# 130811_AriloTX_0_0.net
KiCad netlist of a schematic drawn in EAGLE
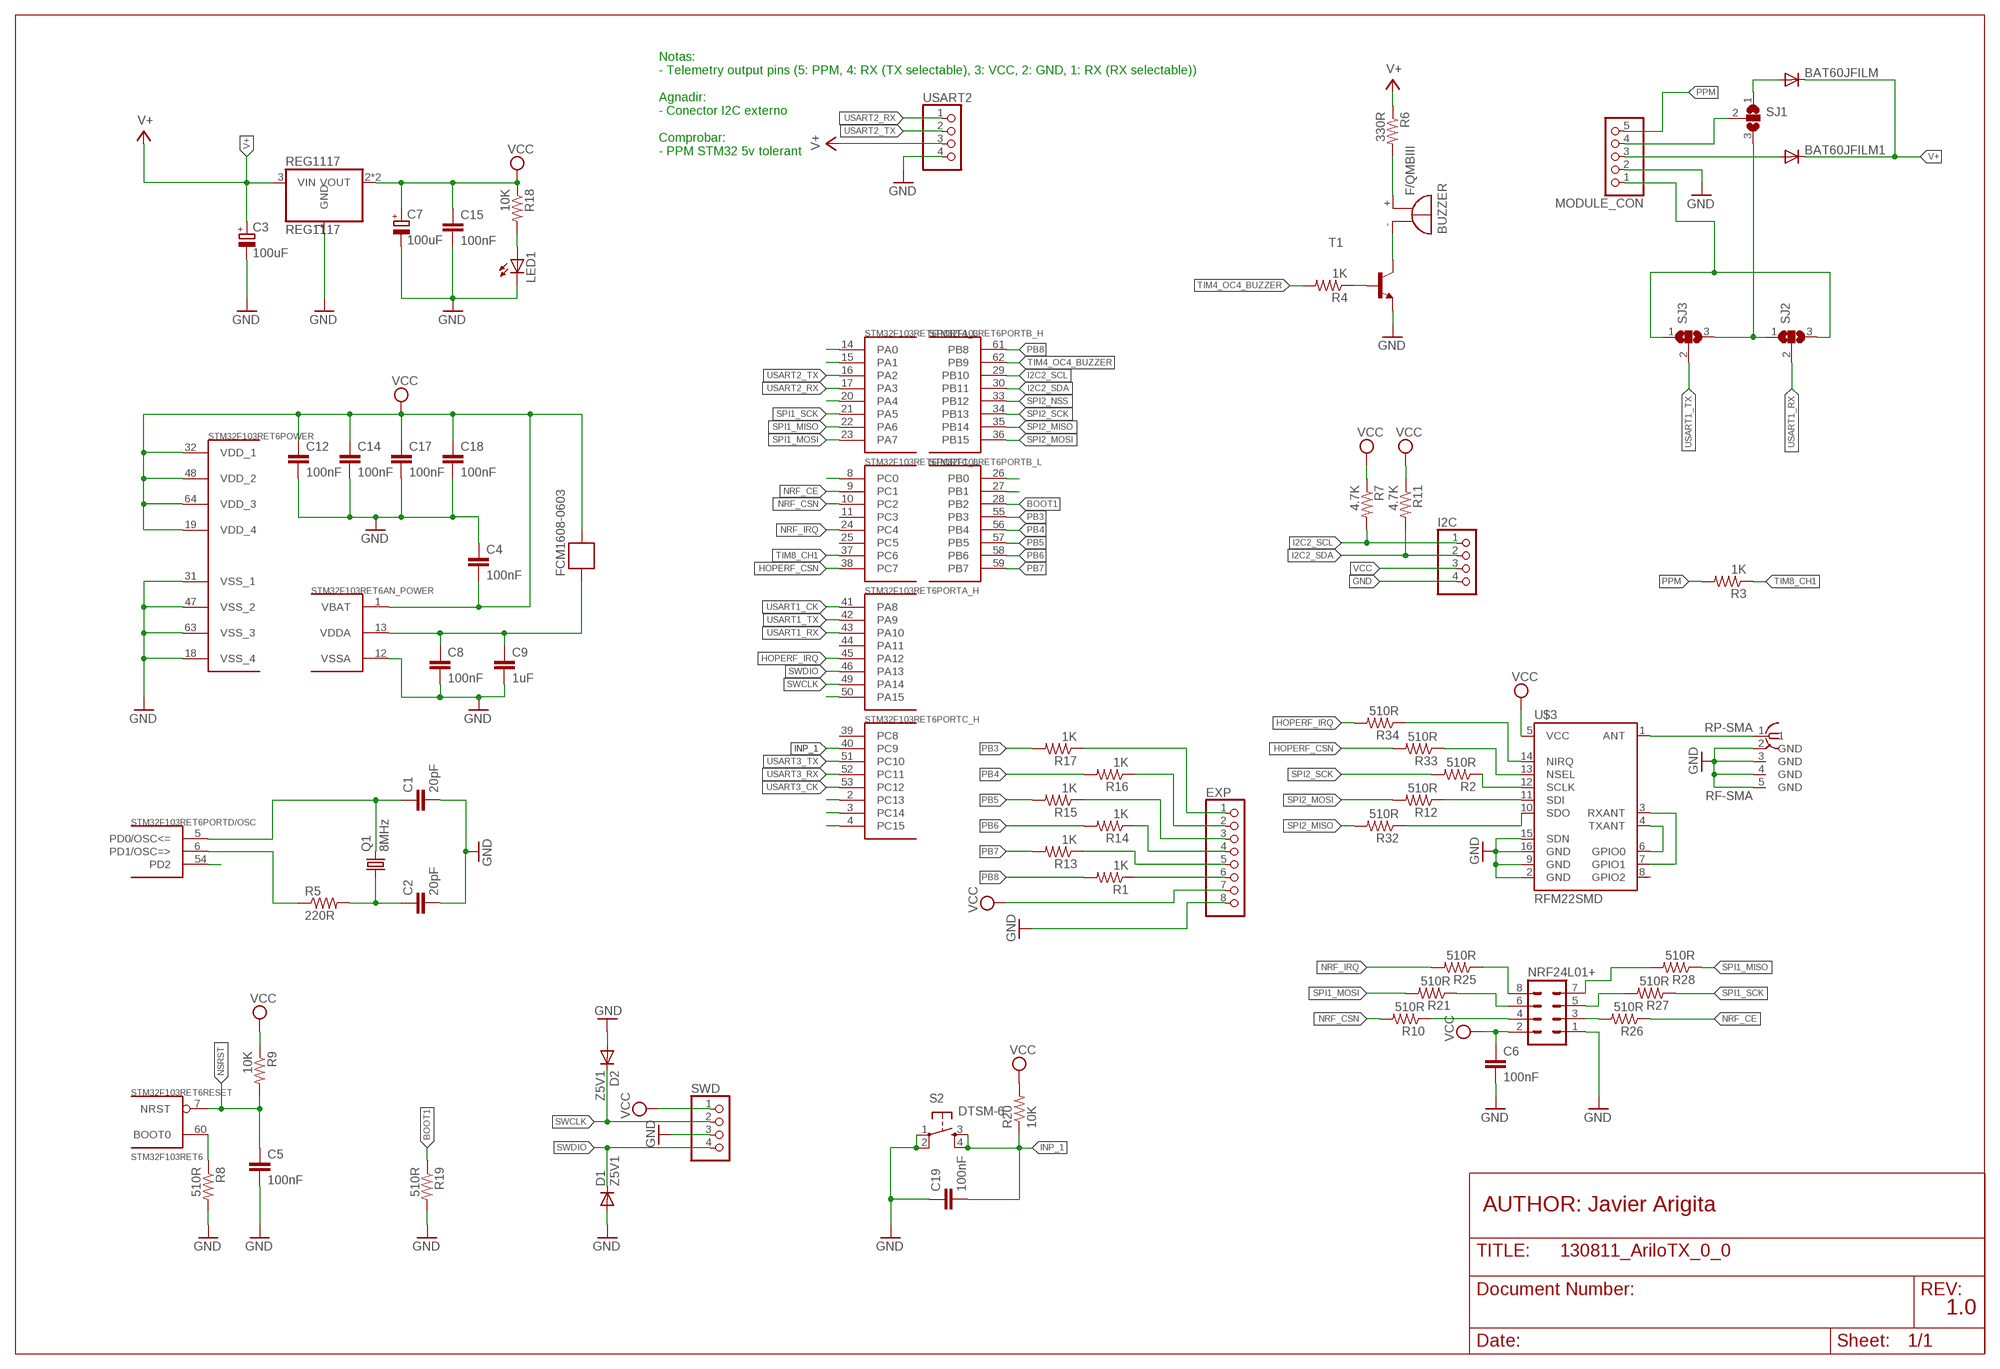
[diagram p0: schematic, sheet 1]

(export (version "E")
  (design (tool "Eeschema 10.0.6"))
  (components
    (comp (ref "BAT60JFILM")
      (value "DIODE-SOD323-R")
      (footprint "eagle-import:SOD323-R")
      (libsource (lib "eagle-import") (part "DIODE-SOD323-R"))
    )
    (comp (ref "BAT60JFILM1")
      (value "DIODE-SOD323-R")
      (footprint "eagle-import:SOD323-R")
      (libsource (lib "eagle-import") (part "DIODE-SOD323-R"))
    )
    (comp (ref "BUZZER")
      (value "F/QMBIII")
      (footprint "eagle-import:F_QMBIII")
      (libsource (lib "eagle-import") (part "F/QMBIII"))
    )
    (comp (ref "C1")
      (value "20pF")
      (footprint "eagle-import:C0805")
      (libsource (lib "eagle-import") (part "C-EUC0805"))
    )
    (comp (ref "C2")
      (value "20pF")
      (footprint "eagle-import:C0805")
      (libsource (lib "eagle-import") (part "C-EUC0805"))
    )
    (comp (ref "C3")
      (value "100uF")
      (footprint "eagle-import:SMC_B")
      (libsource (lib "eagle-import") (part "CPOL-EUSMCB"))
    )
    (comp (ref "C4")
      (value "100nF")
      (footprint "eagle-import:C0805")
      (libsource (lib "eagle-import") (part "C-EUC0805"))
    )
    (comp (ref "C5")
      (value "100nF")
      (footprint "eagle-import:C0805")
      (libsource (lib "eagle-import") (part "C-EUC0805"))
    )
    (comp (ref "C6")
      (value "100nF")
      (footprint "eagle-import:C0805")
      (libsource (lib "eagle-import") (part "C-EUC0805"))
    )
    (comp (ref "C7")
      (value "100uF")
      (footprint "eagle-import:SMC_B")
      (libsource (lib "eagle-import") (part "CPOL-EUSMCB"))
    )
    (comp (ref "C8")
      (value "100nF")
      (footprint "eagle-import:C0805")
      (libsource (lib "eagle-import") (part "C-EUC0805"))
    )
    (comp (ref "C9")
      (value "1uF")
      (footprint "eagle-import:C3216")
      (libsource (lib "eagle-import") (part "resistor_C-EUC3216"))
    )
    (comp (ref "C12")
      (value "100nF")
      (footprint "eagle-import:C0805")
      (libsource (lib "eagle-import") (part "C-EUC0805"))
    )
    (comp (ref "C14")
      (value "100nF")
      (footprint "eagle-import:C0805")
      (libsource (lib "eagle-import") (part "C-EUC0805"))
    )
    (comp (ref "C15")
      (value "100nF")
      (footprint "eagle-import:C0805")
      (libsource (lib "eagle-import") (part "C-EUC0805"))
    )
    (comp (ref "C17")
      (value "100nF")
      (footprint "eagle-import:C0805")
      (libsource (lib "eagle-import") (part "C-EUC0805"))
    )
    (comp (ref "C18")
      (value "100nF")
      (footprint "eagle-import:C0805")
      (libsource (lib "eagle-import") (part "C-EUC0805"))
    )
    (comp (ref "C19")
      (value "100nF")
      (footprint "eagle-import:C0805")
      (libsource (lib "eagle-import") (part "C-EUC0805"))
    )
    (comp (ref "D1")
      (value "Z5V1")
      (footprint "eagle-import:SOD323-R")
      (libsource (lib "eagle-import") (part "DIODE-SOD323-R"))
    )
    (comp (ref "D2")
      (value "Z5V1")
      (footprint "eagle-import:SOD323-R")
      (libsource (lib "eagle-import") (part "DIODE-SOD323-R"))
    )
    (comp (ref "EXP")
      (value "PINHD-1X8")
      (footprint "eagle-import:1X08")
      (libsource (lib "eagle-import") (part "PINHD-1X8"))
    )
    (comp (ref "FCM1608-0603")
      (value "FERRITE-BEAD")
      (footprint "eagle-import:R0603")
      (libsource (lib "eagle-import") (part "FERRITE-BEAD"))
    )
    (comp (ref "I2C")
      (value "PINHD-1X4")
      (footprint "eagle-import:1X04")
      (libsource (lib "eagle-import") (part "PINHD-1X4"))
    )
    (comp (ref "LED1")
      (value "LED0805")
      (footprint "eagle-import:CHIPLED_0805")
      (libsource (lib "eagle-import") (part "LED0805"))
    )
    (comp (ref "MODULE_CON")
      (value "PINHD-1X5")
      (footprint "eagle-import:1X05")
      (libsource (lib "eagle-import") (part "PINHD-1X5"))
    )
    (comp (ref "NRF24L01+")
      (value "MA04-2")
      (footprint "eagle-import:MA04-2")
      (libsource (lib "eagle-import") (part "MA04-2"))
    )
    (comp (ref "Q1")
      (value "8MHz")
      (footprint "eagle-import:SM49")
      (libsource (lib "eagle-import") (part "CRYSTALSM49"))
    )
    (comp (ref "R1")
      (value "1K")
      (footprint "eagle-import:R0805")
      (libsource (lib "eagle-import") (part "RESISTOR0805"))
    )
    (comp (ref "R2")
      (value "510R")
      (footprint "eagle-import:R0805")
      (libsource (lib "eagle-import") (part "RESISTOR0805"))
    )
    (comp (ref "R3")
      (value "1K")
      (footprint "eagle-import:R0805")
      (libsource (lib "eagle-import") (part "RESISTOR0805"))
    )
    (comp (ref "R4")
      (value "1K")
      (footprint "eagle-import:R0805")
      (libsource (lib "eagle-import") (part "RESISTOR0805"))
    )
    (comp (ref "R5")
      (value "220R")
      (footprint "eagle-import:R0805")
      (libsource (lib "eagle-import") (part "RESISTOR0805"))
    )
    (comp (ref "R6")
      (value "330R")
      (footprint "eagle-import:R0805")
      (libsource (lib "eagle-import") (part "RESISTOR0805"))
    )
    (comp (ref "R7")
      (value "4.7K")
      (footprint "eagle-import:R0805")
      (libsource (lib "eagle-import") (part "RESISTOR0805"))
    )
    (comp (ref "R8")
      (value "510R")
      (footprint "eagle-import:R0805")
      (libsource (lib "eagle-import") (part "RESISTOR0805"))
    )
    (comp (ref "R9")
      (value "10K")
      (footprint "eagle-import:R0805")
      (libsource (lib "eagle-import") (part "RESISTOR0805"))
    )
    (comp (ref "R10")
      (value "510R")
      (footprint "eagle-import:R0805")
      (libsource (lib "eagle-import") (part "RESISTOR0805"))
    )
    (comp (ref "R11")
      (value "4.7K")
      (footprint "eagle-import:R0805")
      (libsource (lib "eagle-import") (part "RESISTOR0805"))
    )
    (comp (ref "R12")
      (value "510R")
      (footprint "eagle-import:R0805")
      (libsource (lib "eagle-import") (part "RESISTOR0805"))
    )
    (comp (ref "R13")
      (value "1K")
      (footprint "eagle-import:R0805")
      (libsource (lib "eagle-import") (part "RESISTOR0805"))
    )
    (comp (ref "R14")
      (value "1K")
      (footprint "eagle-import:R0805")
      (libsource (lib "eagle-import") (part "RESISTOR0805"))
    )
    (comp (ref "R15")
      (value "1K")
      (footprint "eagle-import:R0805")
      (libsource (lib "eagle-import") (part "RESISTOR0805"))
    )
    (comp (ref "R16")
      (value "1K")
      (footprint "eagle-import:R0805")
      (libsource (lib "eagle-import") (part "RESISTOR0805"))
    )
    (comp (ref "R17")
      (value "1K")
      (footprint "eagle-import:R0805")
      (libsource (lib "eagle-import") (part "RESISTOR0805"))
    )
    (comp (ref "R18")
      (value "10K")
      (footprint "eagle-import:R0805")
      (libsource (lib "eagle-import") (part "RESISTOR0805"))
    )
    (comp (ref "R19")
      (value "510R")
      (footprint "eagle-import:R0805")
      (libsource (lib "eagle-import") (part "RESISTOR0805"))
    )
    (comp (ref "R20")
      (value "10K")
      (footprint "eagle-import:R0805")
      (libsource (lib "eagle-import") (part "RESISTOR0805"))
    )
    (comp (ref "R21")
      (value "510R")
      (footprint "eagle-import:R0805")
      (libsource (lib "eagle-import") (part "RESISTOR0805"))
    )
    (comp (ref "R25")
      (value "510R")
      (footprint "eagle-import:R0805")
      (libsource (lib "eagle-import") (part "RESISTOR0805"))
    )
    (comp (ref "R26")
      (value "510R")
      (footprint "eagle-import:R0805")
      (libsource (lib "eagle-import") (part "RESISTOR0805"))
    )
    (comp (ref "R27")
      (value "510R")
      (footprint "eagle-import:R0805")
      (libsource (lib "eagle-import") (part "RESISTOR0805"))
    )
    (comp (ref "R28")
      (value "510R")
      (footprint "eagle-import:R0805")
      (libsource (lib "eagle-import") (part "RESISTOR0805"))
    )
    (comp (ref "R32")
      (value "510R")
      (footprint "eagle-import:R0805")
      (libsource (lib "eagle-import") (part "RESISTOR0805"))
    )
    (comp (ref "R33")
      (value "510R")
      (footprint "eagle-import:R0805")
      (libsource (lib "eagle-import") (part "RESISTOR0805"))
    )
    (comp (ref "R34")
      (value "510R")
      (footprint "eagle-import:R0805")
      (libsource (lib "eagle-import") (part "RESISTOR0805"))
    )
    (comp (ref "REG1117")
      (value "REG1117")
      (footprint "eagle-import:SOT223")
      (libsource (lib "eagle-import") (part "REG1117"))
    )
    (comp (ref "RP-SMA")
      (value "RF-SMA")
      (footprint "eagle-import:BU-SMA-H")
      (libsource (lib "eagle-import") (part "RF-SMA"))
    )
    (comp (ref "S2")
      (value "DTSM-6")
      (footprint "eagle-import:DTSM-6")
      (libsource (lib "eagle-import") (part "DTSM-6"))
    )
    (comp (ref "SJ1")
      (value "SJ2W")
      (footprint "eagle-import:SJ_2")
      (libsource (lib "eagle-import") (part "SJ2W"))
    )
    (comp (ref "SJ2")
      (value "SJ2W")
      (footprint "eagle-import:SJ_2")
      (libsource (lib "eagle-import") (part "SJ2W"))
    )
    (comp (ref "SJ3")
      (value "SJ2W")
      (footprint "eagle-import:SJ_2")
      (libsource (lib "eagle-import") (part "SJ2W"))
    )
    (comp (ref "STM32F103RET6")
      (value "STM32F103RET6")
      (footprint "eagle-import:TQFP64")
      (libsource (lib "eagle-import") (part "STM32F10XRXT6"))
    )
    (comp (ref "SWD")
      (value "PINHD-1X4")
      (footprint "eagle-import:1X04")
      (libsource (lib "eagle-import") (part "PINHD-1X4"))
    )
    (comp (ref "T1")
      (value "BC848-NPN-SOT23-BEC")
      (footprint "eagle-import:SOT23-BEC")
      (libsource (lib "eagle-import") (part "-NPN-SOT23-BECBC848"))
    )
    (comp (ref "U$3")
      (value "RFM22SMD")
      (footprint "eagle-import:RFM22-XXX-S2")
      (libsource (lib "eagle-import") (part "RFM22SMD"))
    )
    (comp (ref "USART2")
      (value "PINHD-1X4")
      (footprint "eagle-import:1X04")
      (libsource (lib "eagle-import") (part "PINHD-1X4"))
    )
  )
  (nets
    (net (code "1") (name "BOOT1") (class "Default")
      (node (ref "R19") (pin "1") (pinfunction "1_1") (pintype "passive"))
      (node (ref "STM32F103RET6") (pin "28") (pinfunction "PB2_28") (pintype "bidirectional"))
    )
    (net (code "2") (name "GND") (class "Default")
      (node (ref "C1") (pin "2") (pinfunction "2_2") (pintype "passive"))
      (node (ref "C12") (pin "2") (pinfunction "2_2") (pintype "passive"))
      (node (ref "C14") (pin "2") (pinfunction "2_2") (pintype "passive"))
      (node (ref "C15") (pin "2") (pinfunction "2_2") (pintype "passive"))
      (node (ref "C17") (pin "2") (pinfunction "2_2") (pintype "passive"))
      (node (ref "C18") (pin "2") (pinfunction "2_2") (pintype "passive"))
      (node (ref "C19") (pin "1") (pinfunction "1_1") (pintype "passive"))
      (node (ref "C2") (pin "2") (pinfunction "2_2") (pintype "passive"))
      (node (ref "C3") (pin "-") (pinfunction "-_-") (pintype "passive"))
      (node (ref "C4") (pin "1") (pinfunction "1_1") (pintype "passive"))
      (node (ref "C5") (pin "2") (pinfunction "2_2") (pintype "passive"))
      (node (ref "C6") (pin "2") (pinfunction "2_2") (pintype "passive"))
      (node (ref "C7") (pin "-") (pinfunction "-_-") (pintype "passive"))
      (node (ref "C8") (pin "2") (pinfunction "2_2") (pintype "passive"))
      (node (ref "C9") (pin "2") (pinfunction "2_2") (pintype "passive"))
      (node (ref "D1") (pin "A") (pinfunction "A_A") (pintype "passive"))
      (node (ref "D2") (pin "A") (pinfunction "A_A") (pintype "passive"))
      (node (ref "EXP") (pin "8") (pinfunction "8_8") (pintype "passive"))
      (node (ref "I2C") (pin "4") (pinfunction "4_4") (pintype "passive"))
      (node (ref "LED1") (pin "C") (pinfunction "C_C") (pintype "passive"))
      (node (ref "MODULE_CON") (pin "2") (pinfunction "2_2") (pintype "passive"))
      (node (ref "NRF24L01+") (pin "1") (pinfunction "1_1") (pintype "passive"))
      (node (ref "R19") (pin "2") (pinfunction "2_2") (pintype "passive"))
      (node (ref "R8") (pin "2") (pinfunction "2_2") (pintype "passive"))
      (node (ref "REG1117") (pin "1") (pinfunction "GND_1") (pintype "power_in"))
      (node (ref "RP-SMA") (pin "2") (pinfunction "GND_2") (pintype "power_in"))
      (node (ref "RP-SMA") (pin "3") (pinfunction "GND_3") (pintype "bidirectional"))
      (node (ref "RP-SMA") (pin "4") (pinfunction "GND_4") (pintype "bidirectional"))
      (node (ref "RP-SMA") (pin "5") (pinfunction "GND_5") (pintype "bidirectional"))
      (node (ref "S2") (pin "1") (pinfunction "1_1") (pintype "passive"))
      (node (ref "S2") (pin "2") (pinfunction "2_2") (pintype "passive"))
      (node (ref "STM32F103RET6") (pin "12") (pinfunction "VSSA_12") (pintype "power_in"))
      (node (ref "STM32F103RET6") (pin "18") (pinfunction "VSS_4_18") (pintype "power_in"))
      (node (ref "STM32F103RET6") (pin "31") (pinfunction "VSS_1_31") (pintype "power_in"))
      (node (ref "STM32F103RET6") (pin "47") (pinfunction "VSS_2_47") (pintype "power_in"))
      (node (ref "STM32F103RET6") (pin "63") (pinfunction "VSS_3_63") (pintype "power_in"))
      (node (ref "SWD") (pin "3") (pinfunction "3_3") (pintype "passive"))
      (node (ref "T1") (pin "E") (pinfunction "E_E") (pintype "passive"))
      (node (ref "U$3") (pin "15") (pinfunction "SDN_15") (pintype "input"))
      (node (ref "U$3") (pin "16") (pinfunction "GND_16") (pintype "power_in"))
      (node (ref "U$3") (pin "2") (pinfunction "GND_2") (pintype "power_in"))
      (node (ref "U$3") (pin "9") (pinfunction "GND_9") (pintype "power_in"))
      (node (ref "USART2") (pin "4") (pinfunction "4_4") (pintype "passive"))
    )
    (net (code "3") (name "HOPERF_CSN") (class "Default")
      (node (ref "R33") (pin "2") (pinfunction "2_2") (pintype "passive"))
      (node (ref "STM32F103RET6") (pin "38") (pinfunction "PC7_38") (pintype "bidirectional"))
    )
    (net (code "4") (name "HOPERF_IRQ") (class "Default")
      (node (ref "R34") (pin "2") (pinfunction "2_2") (pintype "passive"))
      (node (ref "STM32F103RET6") (pin "45") (pinfunction "PA12_45") (pintype "bidirectional"))
    )
    (net (code "5") (name "I2C2_SCL") (class "Default")
      (node (ref "I2C") (pin "1") (pinfunction "1_1") (pintype "passive"))
      (node (ref "R7") (pin "2") (pinfunction "2_2") (pintype "passive"))
      (node (ref "STM32F103RET6") (pin "29") (pinfunction "PB10_29") (pintype "bidirectional"))
    )
    (net (code "6") (name "I2C2_SDA") (class "Default")
      (node (ref "I2C") (pin "2") (pinfunction "2_2") (pintype "passive"))
      (node (ref "R11") (pin "2") (pinfunction "2_2") (pintype "passive"))
      (node (ref "STM32F103RET6") (pin "30") (pinfunction "PB11_30") (pintype "bidirectional"))
    )
    (net (code "7") (name "INP_1") (class "Default")
      (node (ref "C19") (pin "2") (pinfunction "2_2") (pintype "passive"))
      (node (ref "R20") (pin "1") (pinfunction "1_1") (pintype "passive"))
      (node (ref "S2") (pin "3") (pinfunction "3_3") (pintype "passive"))
      (node (ref "S2") (pin "4") (pinfunction "4_4") (pintype "passive"))
      (node (ref "STM32F103RET6") (pin "40") (pinfunction "PC9_40") (pintype "bidirectional"))
    )
    (net (code "8") (name "NRF_CE") (class "Default")
      (node (ref "R26") (pin "1") (pinfunction "1_1") (pintype "passive"))
      (node (ref "STM32F103RET6") (pin "9") (pinfunction "PC1_9") (pintype "bidirectional"))
    )
    (net (code "9") (name "NRF_CSN") (class "Default")
      (node (ref "R10") (pin "2") (pinfunction "2_2") (pintype "passive"))
      (node (ref "STM32F103RET6") (pin "10") (pinfunction "PC2_10") (pintype "bidirectional"))
    )
    (net (code "10") (name "NRF_IRQ") (class "Default")
      (node (ref "R25") (pin "2") (pinfunction "2_2") (pintype "passive"))
      (node (ref "STM32F103RET6") (pin "24") (pinfunction "PC4_24") (pintype "bidirectional"))
    )
    (net (code "11") (name "NSRST") (class "Default")
      (node (ref "C5") (pin "1") (pinfunction "1_1") (pintype "passive"))
      (node (ref "R9") (pin "2") (pinfunction "2_2") (pintype "passive"))
      (node (ref "STM32F103RET6") (pin "7") (pinfunction "NRST_7") (pintype "input"))
    )
    (net (code "12") (name "Net-(BAT60JFILM-PadA)") (class "Default")
      (node (ref "BAT60JFILM") (pin "A") (pinfunction "A_A") (pintype "passive"))
      (node (ref "SJ1") (pin "1") (pinfunction "1_1") (pintype "passive"))
    )
    (net (code "13") (name "Net-(BAT60JFILM1-PadA)") (class "Default")
      (node (ref "BAT60JFILM1") (pin "A") (pinfunction "A_A") (pintype "passive"))
      (node (ref "MODULE_CON") (pin "3") (pinfunction "3_3") (pintype "passive"))
    )
    (net (code "14") (name "Net-(BUZZER-+)") (class "Default")
      (node (ref "BUZZER") (pin "-") (pinfunction "+_-") (pintype "passive"))
      (node (ref "T1") (pin "C") (pinfunction "C_C") (pintype "passive"))
    )
    (net (code "15") (name "Net-(BUZZER--)") (class "Default")
      (node (ref "BUZZER") (pin "+") (pinfunction "-_+") (pintype "passive"))
      (node (ref "R6") (pin "2") (pinfunction "2_2") (pintype "passive"))
    )
    (net (code "16") (name "Net-(C2-Pad1)") (class "Default")
      (node (ref "C2") (pin "1") (pinfunction "1_1") (pintype "passive"))
      (node (ref "Q1") (pin "1") (pinfunction "1_1") (pintype "passive"))
      (node (ref "R5") (pin "2") (pinfunction "2_2") (pintype "passive"))
    )
    (net (code "17") (name "Net-(EXP-Pad1)") (class "Default")
      (node (ref "EXP") (pin "1") (pinfunction "1_1") (pintype "passive"))
      (node (ref "R17") (pin "1") (pinfunction "1_1") (pintype "passive"))
    )
    (net (code "18") (name "Net-(EXP-Pad2)") (class "Default")
      (node (ref "EXP") (pin "2") (pinfunction "2_2") (pintype "passive"))
      (node (ref "R16") (pin "1") (pinfunction "1_1") (pintype "passive"))
    )
    (net (code "19") (name "Net-(EXP-Pad3)") (class "Default")
      (node (ref "EXP") (pin "3") (pinfunction "3_3") (pintype "passive"))
      (node (ref "R15") (pin "1") (pinfunction "1_1") (pintype "passive"))
    )
    (net (code "20") (name "Net-(EXP-Pad4)") (class "Default")
      (node (ref "EXP") (pin "4") (pinfunction "4_4") (pintype "passive"))
      (node (ref "R14") (pin "1") (pinfunction "1_1") (pintype "passive"))
    )
    (net (code "21") (name "Net-(EXP-Pad5)") (class "Default")
      (node (ref "EXP") (pin "5") (pinfunction "5_5") (pintype "passive"))
      (node (ref "R13") (pin "1") (pinfunction "1_1") (pintype "passive"))
    )
    (net (code "22") (name "Net-(EXP-Pad6)") (class "Default")
      (node (ref "EXP") (pin "6") (pinfunction "6_6") (pintype "passive"))
      (node (ref "R1") (pin "1") (pinfunction "1_1") (pintype "passive"))
    )
    (net (code "23") (name "Net-(FCM1608-0603-P$2)") (class "Default")
      (node (ref "C8") (pin "1") (pinfunction "1_1") (pintype "passive"))
      (node (ref "C9") (pin "1") (pinfunction "1_1") (pintype "passive"))
      (node (ref "FCM1608-0603") (pin "2") (pinfunction "P$2_2") (pintype "bidirectional"))
      (node (ref "STM32F103RET6") (pin "13") (pinfunction "VDDA_13") (pintype "power_in"))
    )
    (net (code "24") (name "Net-(LED1-PadA)") (class "Default")
      (node (ref "LED1") (pin "A") (pinfunction "A_A") (pintype "passive"))
      (node (ref "R18") (pin "2") (pinfunction "2_2") (pintype "passive"))
    )
    (net (code "25") (name "Net-(MODULE_CON-Pad1)") (class "Default")
      (node (ref "MODULE_CON") (pin "1") (pinfunction "1_1") (pintype "passive"))
      (node (ref "SJ2") (pin "3") (pinfunction "3_3") (pintype "passive"))
      (node (ref "SJ3") (pin "1") (pinfunction "1_1") (pintype "passive"))
    )
    (net (code "26") (name "Net-(MODULE_CON-Pad4)") (class "Default")
      (node (ref "MODULE_CON") (pin "4") (pinfunction "4_4") (pintype "passive"))
      (node (ref "SJ1") (pin "2") (pinfunction "2_2") (pintype "passive"))
    )
    (net (code "27") (name "Net-(NRF24L01+-Pad3)") (class "Default")
      (node (ref "NRF24L01+") (pin "3") (pinfunction "3_3") (pintype "passive"))
      (node (ref "R26") (pin "2") (pinfunction "2_2") (pintype "passive"))
    )
    (net (code "28") (name "Net-(NRF24L01+-Pad4)") (class "Default")
      (node (ref "NRF24L01+") (pin "4") (pinfunction "4_4") (pintype "passive"))
      (node (ref "R10") (pin "1") (pinfunction "1_1") (pintype "passive"))
    )
    (net (code "29") (name "Net-(NRF24L01+-Pad5)") (class "Default")
      (node (ref "NRF24L01+") (pin "5") (pinfunction "5_5") (pintype "passive"))
      (node (ref "R27") (pin "2") (pinfunction "2_2") (pintype "passive"))
    )
    (net (code "30") (name "Net-(NRF24L01+-Pad6)") (class "Default")
      (node (ref "NRF24L01+") (pin "6") (pinfunction "6_6") (pintype "passive"))
      (node (ref "R21") (pin "1") (pinfunction "1_1") (pintype "passive"))
    )
    (net (code "31") (name "Net-(NRF24L01+-Pad7)") (class "Default")
      (node (ref "NRF24L01+") (pin "7") (pinfunction "7_7") (pintype "passive"))
      (node (ref "R28") (pin "2") (pinfunction "2_2") (pintype "passive"))
    )
    (net (code "32") (name "Net-(NRF24L01+-Pad8)") (class "Default")
      (node (ref "NRF24L01+") (pin "8") (pinfunction "8_8") (pintype "passive"))
      (node (ref "R25") (pin "1") (pinfunction "1_1") (pintype "passive"))
    )
    (net (code "33") (name "Net-(R4-Pad1)") (class "Default")
      (node (ref "R4") (pin "1") (pinfunction "1_1") (pintype "passive"))
      (node (ref "T1") (pin "B") (pinfunction "B_B") (pintype "passive"))
    )
    (net (code "34") (name "Net-(SJ1-Pad3)") (class "Default")
      (node (ref "SJ1") (pin "3") (pinfunction "3_3") (pintype "passive"))
      (node (ref "SJ2") (pin "1") (pinfunction "1_1") (pintype "passive"))
      (node (ref "SJ3") (pin "3") (pinfunction "3_3") (pintype "passive"))
    )
    (net (code "35") (name "Net-(STM32F103RET6H-PD0{slash}OSC<=)") (class "Default")
      (node (ref "C1") (pin "1") (pinfunction "1_1") (pintype "passive"))
      (node (ref "Q1") (pin "2") (pinfunction "2_2") (pintype "passive"))
      (node (ref "STM32F103RET6") (pin "5") (pinfunction "PD0/OSC<=_5") (pintype "bidirectional"))
    )
    (net (code "36") (name "Net-(STM32F103RET6H-PD1{slash}OSC=>)") (class "Default")
      (node (ref "R5") (pin "1") (pinfunction "1_1") (pintype "passive"))
      (node (ref "STM32F103RET6") (pin "6") (pinfunction "PD1/OSC=>_6") (pintype "bidirectional"))
    )
    (net (code "37") (name "Net-(STM32F103RET6J-BOOT0)") (class "Default")
      (node (ref "R8") (pin "1") (pinfunction "1_1") (pintype "passive"))
      (node (ref "STM32F103RET6") (pin "60") (pinfunction "BOOT0_60") (pintype "input"))
    )
    (net (code "38") (name "Net-(U$3-ANT)") (class "Default")
      (node (ref "RP-SMA") (pin "1") (pinfunction "1_1") (pintype "passive"))
      (node (ref "U$3") (pin "1") (pinfunction "ANT_1") (pintype "bidirectional"))
    )
    (net (code "39") (name "Net-(U$3-GPIO0)") (class "Default")
      (node (ref "U$3") (pin "4") (pinfunction "TXANT_4") (pintype "input"))
      (node (ref "U$3") (pin "6") (pinfunction "GPIO0_6") (pintype "bidirectional"))
    )
    (net (code "40") (name "Net-(U$3-GPIO1)") (class "Default")
      (node (ref "U$3") (pin "3") (pinfunction "RXANT_3") (pintype "input"))
      (node (ref "U$3") (pin "7") (pinfunction "GPIO1_7") (pintype "bidirectional"))
    )
    (net (code "41") (name "Net-(U$3-NIRQ)") (class "Default")
      (node (ref "R34") (pin "1") (pinfunction "1_1") (pintype "passive"))
      (node (ref "U$3") (pin "14") (pinfunction "NIRQ_14") (pintype "output"))
    )
    (net (code "42") (name "Net-(U$3-NSEL)") (class "Default")
      (node (ref "R33") (pin "1") (pinfunction "1_1") (pintype "passive"))
      (node (ref "U$3") (pin "13") (pinfunction "NSEL_13") (pintype "input"))
    )
    (net (code "43") (name "Net-(U$3-SCLK)") (class "Default")
      (node (ref "R2") (pin "1") (pinfunction "1_1") (pintype "passive"))
      (node (ref "U$3") (pin "12") (pinfunction "SCLK_12") (pintype "input"))
    )
    (net (code "44") (name "Net-(U$3-SDI)") (class "Default")
      (node (ref "R12") (pin "1") (pinfunction "1_1") (pintype "passive"))
      (node (ref "U$3") (pin "11") (pinfunction "SDI_11") (pintype "input"))
    )
    (net (code "45") (name "Net-(U$3-SDO)") (class "Default")
      (node (ref "R32") (pin "1") (pinfunction "1_1") (pintype "passive"))
      (node (ref "U$3") (pin "10") (pinfunction "SDO_10") (pintype "output"))
    )
    (net (code "46") (name "PB3") (class "Default")
      (node (ref "R17") (pin "2") (pinfunction "2_2") (pintype "passive"))
      (node (ref "STM32F103RET6") (pin "55") (pinfunction "PB3_55") (pintype "bidirectional"))
    )
    (net (code "47") (name "PB4") (class "Default")
      (node (ref "R16") (pin "2") (pinfunction "2_2") (pintype "passive"))
      (node (ref "STM32F103RET6") (pin "56") (pinfunction "PB4_56") (pintype "bidirectional"))
    )
    (net (code "48") (name "PB5") (class "Default")
      (node (ref "R15") (pin "2") (pinfunction "2_2") (pintype "passive"))
      (node (ref "STM32F103RET6") (pin "57") (pinfunction "PB5_57") (pintype "bidirectional"))
    )
    (net (code "49") (name "PB6") (class "Default")
      (node (ref "R14") (pin "2") (pinfunction "2_2") (pintype "passive"))
      (node (ref "STM32F103RET6") (pin "58") (pinfunction "PB6_58") (pintype "bidirectional"))
    )
    (net (code "50") (name "PB7") (class "Default")
      (node (ref "R13") (pin "2") (pinfunction "2_2") (pintype "passive"))
      (node (ref "STM32F103RET6") (pin "59") (pinfunction "PB7_59") (pintype "bidirectional"))
    )
    (net (code "51") (name "PB8") (class "Default")
      (node (ref "R1") (pin "2") (pinfunction "2_2") (pintype "passive"))
      (node (ref "STM32F103RET6") (pin "61") (pinfunction "PB8_61") (pintype "bidirectional"))
    )
    (net (code "52") (name "PPM") (class "Default")
      (node (ref "MODULE_CON") (pin "5") (pinfunction "5_5") (pintype "passive"))
      (node (ref "R3") (pin "2") (pinfunction "2_2") (pintype "passive"))
    )
    (net (code "53") (name "SPI1_MISO") (class "Default")
      (node (ref "R28") (pin "1") (pinfunction "1_1") (pintype "passive"))
      (node (ref "STM32F103RET6") (pin "22") (pinfunction "PA6_22") (pintype "bidirectional"))
    )
    (net (code "54") (name "SPI1_MOSI") (class "Default")
      (node (ref "R21") (pin "2") (pinfunction "2_2") (pintype "passive"))
      (node (ref "STM32F103RET6") (pin "23") (pinfunction "PA7_23") (pintype "bidirectional"))
    )
    (net (code "55") (name "SPI1_SCK") (class "Default")
      (node (ref "R27") (pin "1") (pinfunction "1_1") (pintype "passive"))
      (node (ref "STM32F103RET6") (pin "21") (pinfunction "PA5_21") (pintype "bidirectional"))
    )
    (net (code "56") (name "SPI2_MISO") (class "Default")
      (node (ref "R32") (pin "2") (pinfunction "2_2") (pintype "passive"))
      (node (ref "STM32F103RET6") (pin "35") (pinfunction "PB14_35") (pintype "bidirectional"))
    )
    (net (code "57") (name "SPI2_MOSI") (class "Default")
      (node (ref "R12") (pin "2") (pinfunction "2_2") (pintype "passive"))
      (node (ref "STM32F103RET6") (pin "36") (pinfunction "PB15_36") (pintype "bidirectional"))
    )
    (net (code "58") (name "SPI2_NSS") (class "Default")
      (node (ref "STM32F103RET6") (pin "33") (pinfunction "PB12_33") (pintype "bidirectional"))
    )
    (net (code "59") (name "SPI2_SCK") (class "Default")
      (node (ref "R2") (pin "2") (pinfunction "2_2") (pintype "passive"))
      (node (ref "STM32F103RET6") (pin "34") (pinfunction "PB13_34") (pintype "bidirectional"))
    )
    (net (code "60") (name "SWCLK") (class "Default")
      (node (ref "D2") (pin "C") (pinfunction "C_C") (pintype "passive"))
      (node (ref "STM32F103RET6") (pin "49") (pinfunction "PA14_49") (pintype "bidirectional"))
      (node (ref "SWD") (pin "2") (pinfunction "2_2") (pintype "passive"))
    )
    (net (code "61") (name "SWDIO") (class "Default")
      (node (ref "D1") (pin "C") (pinfunction "C_C") (pintype "passive"))
      (node (ref "STM32F103RET6") (pin "46") (pinfunction "PA13_46") (pintype "bidirectional"))
      (node (ref "SWD") (pin "4") (pinfunction "4_4") (pintype "passive"))
    )
    (net (code "62") (name "TIM4_OC4_BUZZER") (class "Default")
      (node (ref "R4") (pin "2") (pinfunction "2_2") (pintype "passive"))
      (node (ref "STM32F103RET6") (pin "62") (pinfunction "PB9_62") (pintype "bidirectional"))
    )
    (net (code "63") (name "TIM8_CH1") (class "Default")
      (node (ref "R3") (pin "1") (pinfunction "1_1") (pintype "passive"))
      (node (ref "STM32F103RET6") (pin "37") (pinfunction "PC6_37") (pintype "bidirectional"))
    )
    (net (code "64") (name "USART1_CK") (class "Default")
      (node (ref "STM32F103RET6") (pin "41") (pinfunction "PA8_41") (pintype "bidirectional"))
    )
    (net (code "65") (name "USART1_RX") (class "Default")
      (node (ref "SJ2") (pin "2") (pinfunction "2_2") (pintype "passive"))
      (node (ref "STM32F103RET6") (pin "43") (pinfunction "PA10_43") (pintype "bidirectional"))
    )
    (net (code "66") (name "USART1_TX") (class "Default")
      (node (ref "SJ3") (pin "2") (pinfunction "2_2") (pintype "passive"))
      (node (ref "STM32F103RET6") (pin "42") (pinfunction "PA9_42") (pintype "bidirectional"))
    )
    (net (code "67") (name "USART2_RX") (class "Default")
      (node (ref "STM32F103RET6") (pin "17") (pinfunction "PA3_17") (pintype "bidirectional"))
      (node (ref "USART2") (pin "1") (pinfunction "1_1") (pintype "passive"))
    )
    (net (code "68") (name "USART2_TX") (class "Default")
      (node (ref "STM32F103RET6") (pin "16") (pinfunction "PA2_16") (pintype "bidirectional"))
      (node (ref "USART2") (pin "2") (pinfunction "2_2") (pintype "passive"))
    )
    (net (code "69") (name "USART3_CK") (class "Default")
      (node (ref "STM32F103RET6") (pin "53") (pinfunction "PC12_53") (pintype "bidirectional"))
    )
    (net (code "70") (name "USART3_RX") (class "Default")
      (node (ref "STM32F103RET6") (pin "52") (pinfunction "PC11_52") (pintype "bidirectional"))
    )
    (net (code "71") (name "USART3_TX") (class "Default")
      (node (ref "STM32F103RET6") (pin "51") (pinfunction "PC10_51") (pintype "bidirectional"))
    )
    (net (code "72") (name "V+") (class "Default")
      (node (ref "BAT60JFILM") (pin "C") (pinfunction "C_C") (pintype "passive"))
      (node (ref "BAT60JFILM1") (pin "C") (pinfunction "C_C") (pintype "passive"))
      (node (ref "C3") (pin "+") (pinfunction "+_+") (pintype "passive"))
      (node (ref "R6") (pin "1") (pinfunction "1_1") (pintype "passive"))
      (node (ref "REG1117") (pin "3") (pinfunction "VIN_3") (pintype "input"))
      (node (ref "USART2") (pin "3") (pinfunction "3_3") (pintype "passive"))
    )
    (net (code "73") (name "VCC") (class "Default")
      (node (ref "C12") (pin "1") (pinfunction "1_1") (pintype "passive"))
      (node (ref "C14") (pin "1") (pinfunction "1_1") (pintype "passive"))
      (node (ref "C15") (pin "1") (pinfunction "1_1") (pintype "passive"))
      (node (ref "C17") (pin "1") (pinfunction "1_1") (pintype "passive"))
      (node (ref "C18") (pin "1") (pinfunction "1_1") (pintype "passive"))
      (node (ref "C4") (pin "2") (pinfunction "2_2") (pintype "passive"))
      (node (ref "C6") (pin "1") (pinfunction "1_1") (pintype "passive"))
      (node (ref "C7") (pin "+") (pinfunction "+_+") (pintype "passive"))
      (node (ref "EXP") (pin "7") (pinfunction "7_7") (pintype "passive"))
      (node (ref "FCM1608-0603") (pin "1") (pinfunction "P$1_1") (pintype "bidirectional"))
      (node (ref "I2C") (pin "3") (pinfunction "3_3") (pintype "passive"))
      (node (ref "NRF24L01+") (pin "2") (pinfunction "2_2") (pintype "passive"))
      (node (ref "R11") (pin "1") (pinfunction "1_1") (pintype "passive"))
      (node (ref "R18") (pin "1") (pinfunction "1_1") (pintype "passive"))
      (node (ref "R20") (pin "2") (pinfunction "2_2") (pintype "passive"))
      (node (ref "R7") (pin "1") (pinfunction "1_1") (pintype "passive"))
      (node (ref "R9") (pin "1") (pinfunction "1_1") (pintype "passive"))
      (node (ref "REG1117") (pin "2") (pinfunction "VOUT_2") (pintype "power_in"))
      (node (ref "REG1117") (pin "4") (pinfunction "VOUT_4") (pintype "power_in"))
      (node (ref "STM32F103RET6") (pin "1") (pinfunction "VBAT_1") (pintype "power_in"))
      (node (ref "STM32F103RET6") (pin "19") (pinfunction "VDD_4_19") (pintype "power_in"))
      (node (ref "STM32F103RET6") (pin "32") (pinfunction "VDD_1_32") (pintype "power_in"))
      (node (ref "STM32F103RET6") (pin "48") (pinfunction "VDD_2_48") (pintype "power_in"))
      (node (ref "STM32F103RET6") (pin "64") (pinfunction "VDD_3_64") (pintype "power_in"))
      (node (ref "SWD") (pin "1") (pinfunction "1_1") (pintype "passive"))
      (node (ref "U$3") (pin "5") (pinfunction "VCC_5") (pintype "bidirectional"))
    )
    (net (code "74") (name "unconnected-(STM32F103RET6B-PA11-Pad44)") (class "Default")
      (node (ref "STM32F103RET6") (pin "44") (pinfunction "PA11_44") (pintype "bidirectional"))
    )
    (net (code "75") (name "unconnected-(STM32F103RET6B-PA15-Pad50)") (class "Default")
      (node (ref "STM32F103RET6") (pin "50") (pinfunction "PA15_50") (pintype "bidirectional"))
    )
    (net (code "76") (name "unconnected-(STM32F103RET6C-PA0-Pad14)") (class "Default")
      (node (ref "STM32F103RET6") (pin "14") (pinfunction "PA0_14") (pintype "bidirectional"))
    )
    (net (code "77") (name "unconnected-(STM32F103RET6C-PA1-Pad15)") (class "Default")
      (node (ref "STM32F103RET6") (pin "15") (pinfunction "PA1_15") (pintype "bidirectional"))
    )
    (net (code "78") (name "unconnected-(STM32F103RET6C-PA4-Pad20)") (class "Default")
      (node (ref "STM32F103RET6") (pin "20") (pinfunction "PA4_20") (pintype "bidirectional"))
    )
    (net (code "79") (name "unconnected-(STM32F103RET6E-PB0-Pad26)") (class "Default")
      (node (ref "STM32F103RET6") (pin "26") (pinfunction "PB0_26") (pintype "bidirectional"))
    )
    (net (code "80") (name "unconnected-(STM32F103RET6E-PB1-Pad27)") (class "Default")
      (node (ref "STM32F103RET6") (pin "27") (pinfunction "PB1_27") (pintype "bidirectional"))
    )
    (net (code "81") (name "unconnected-(STM32F103RET6F-PC8-Pad39)") (class "Default")
      (node (ref "STM32F103RET6") (pin "39") (pinfunction "PC8_39") (pintype "bidirectional"))
    )
    (net (code "82") (name "unconnected-(STM32F103RET6F-PC13-Pad2)") (class "Default")
      (node (ref "STM32F103RET6") (pin "2") (pinfunction "PC13_2") (pintype "bidirectional"))
    )
    (net (code "83") (name "unconnected-(STM32F103RET6F-PC14-Pad3)") (class "Default")
      (node (ref "STM32F103RET6") (pin "3") (pinfunction "PC14_3") (pintype "bidirectional"))
    )
    (net (code "84") (name "unconnected-(STM32F103RET6F-PC15-Pad4)") (class "Default")
      (node (ref "STM32F103RET6") (pin "4") (pinfunction "PC15_4") (pintype "bidirectional"))
    )
    (net (code "85") (name "unconnected-(STM32F103RET6G-PC0-Pad8)") (class "Default")
      (node (ref "STM32F103RET6") (pin "8") (pinfunction "PC0_8") (pintype "bidirectional"))
    )
    (net (code "86") (name "unconnected-(STM32F103RET6G-PC3-Pad11)") (class "Default")
      (node (ref "STM32F103RET6") (pin "11") (pinfunction "PC3_11") (pintype "bidirectional"))
    )
    (net (code "87") (name "unconnected-(STM32F103RET6G-PC5-Pad25)") (class "Default")
      (node (ref "STM32F103RET6") (pin "25") (pinfunction "PC5_25") (pintype "bidirectional"))
    )
    (net (code "88") (name "unconnected-(STM32F103RET6H-PD2-Pad54)") (class "Default")
      (node (ref "STM32F103RET6") (pin "54") (pinfunction "PD2_54") (pintype "bidirectional"))
    )
    (net (code "89") (name "unconnected-(U$3-GPIO2-Pad8)") (class "Default")
      (node (ref "U$3") (pin "8") (pinfunction "GPIO2_8") (pintype "bidirectional"))
    )
  )
)
